# signal-1btn.net
KiCad netlist of a schematic drawn in EAGLE
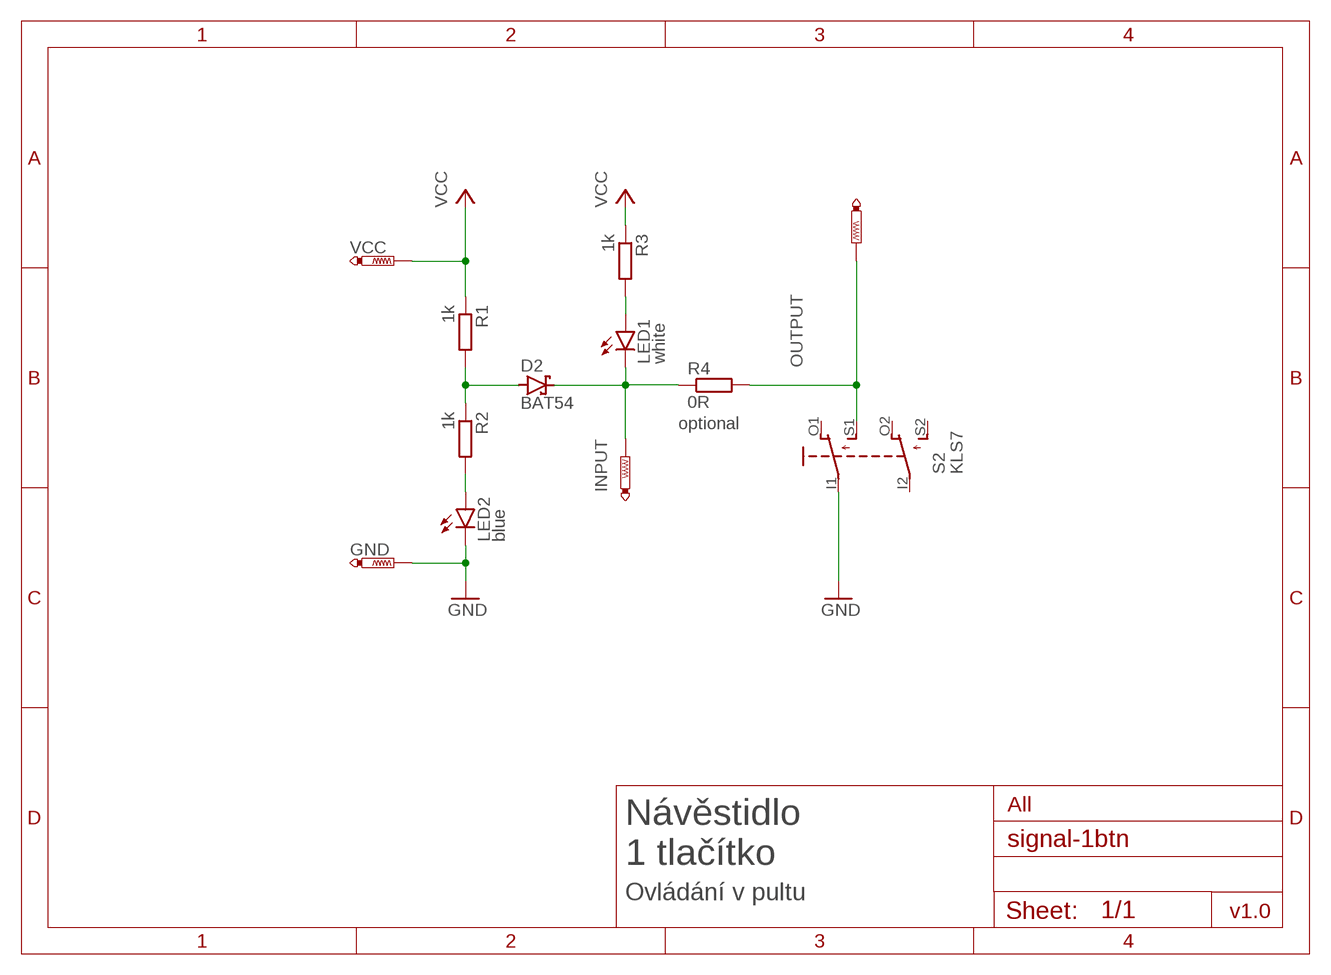
[diagram p0: schematic, sheet 1]

(export (version "E")
  (design (tool "Eeschema 10.0.6"))
  (components
    (comp (ref "D2")
      (value "BAT54")
      (footprint "eagle-import:SOT23")
      (libsource (lib "eagle-import") (part "BAT54"))
    )
    (comp (ref "GND")
      (value "PTR1PAD1-13Y")
      (footprint "eagle-import:P1-13Y")
      (libsource (lib "eagle-import") (part "PTR1PAD1-13Y"))
    )
    (comp (ref "LED1")
      (value "white")
      (footprint "eagle-import:LED3MM")
      (libsource (lib "eagle-import") (part "LED3MM"))
    )
    (comp (ref "LED2")
      (value "blue")
      (footprint "eagle-import:LED3MM")
      (libsource (lib "eagle-import") (part "LED3MM"))
    )
    (comp (ref "P_ACTIVE")
      (value "PTR1PAD1-13Y")
      (footprint "eagle-import:P1-13Y")
      (libsource (lib "eagle-import") (part "PTR1PAD1-13Y"))
    )
    (comp (ref "P_ACTIVE1")
      (value "PTR1PAD1-13Y")
      (footprint "eagle-import:P1-13Y")
      (libsource (lib "eagle-import") (part "PTR1PAD1-13Y"))
    )
    (comp (ref "R1")
      (value "1k")
      (footprint "eagle-import:R0805")
      (libsource (lib "eagle-import") (part "R-EU_R0805"))
    )
    (comp (ref "R2")
      (value "1k")
      (footprint "eagle-import:R0805")
      (libsource (lib "eagle-import") (part "R-EU_R0805"))
    )
    (comp (ref "R3")
      (value "1k")
      (footprint "eagle-import:R0805")
      (libsource (lib "eagle-import") (part "R-EU_R0805"))
    )
    (comp (ref "R4")
      (value "0R")
      (footprint "eagle-import:R0805")
      (libsource (lib "eagle-import") (part "R-EU_R0805"))
    )
    (comp (ref "S2")
      (value "KLS7")
      (footprint "eagle-import:KLS7")
      (libsource (lib "eagle-import") (part "KLS7"))
    )
    (comp (ref "VCC")
      (value "PTR1PAD1-13Y")
      (footprint "eagle-import:P1-13Y")
      (libsource (lib "eagle-import") (part "PTR1PAD1-13Y"))
    )
  )
  (nets
    (net (code "1") (name "/INPUT") (class "Default")
      (node (ref "D2") (pin "3") (pinfunction "C_3") (pintype "passive"))
      (node (ref "LED1") (pin "K") (pinfunction "C_K") (pintype "passive"))
      (node (ref "P_ACTIVE1") (pin "TP") (pinfunction "TP_TP") (pintype "input"))
      (node (ref "R4") (pin "1") (pinfunction "1_1") (pintype "passive"))
    )
    (net (code "2") (name "/OUTPUT") (class "Default")
      (node (ref "P_ACTIVE") (pin "TP") (pinfunction "TP_TP") (pintype "input"))
      (node (ref "R4") (pin "2") (pinfunction "2_2") (pintype "passive"))
      (node (ref "S2") (pin "S1") (pinfunction "S_S1") (pintype "passive"))
    )
    (net (code "3") (name "GND") (class "Default")
      (node (ref "GND") (pin "TP") (pinfunction "TP_TP") (pintype "input"))
      (node (ref "LED2") (pin "K") (pinfunction "C_K") (pintype "passive"))
      (node (ref "S2") (pin "I1") (pinfunction "P_I1") (pintype "passive"))
    )
    (net (code "4") (name "Net-(D2-A)") (class "Default")
      (node (ref "D2") (pin "1") (pinfunction "A_1") (pintype "passive"))
      (node (ref "R1") (pin "2") (pinfunction "2_2") (pintype "passive"))
      (node (ref "R2") (pin "1") (pinfunction "1_1") (pintype "passive"))
    )
    (net (code "5") (name "Net-(LED1-PadA)") (class "Default")
      (node (ref "LED1") (pin "A") (pinfunction "A_A") (pintype "passive"))
      (node (ref "R3") (pin "2") (pinfunction "2_2") (pintype "passive"))
    )
    (net (code "6") (name "Net-(LED2-PadA)") (class "Default")
      (node (ref "LED2") (pin "A") (pinfunction "A_A") (pintype "passive"))
      (node (ref "R2") (pin "2") (pinfunction "2_2") (pintype "passive"))
    )
    (net (code "7") (name "VCC") (class "Default")
      (node (ref "R1") (pin "1") (pinfunction "1_1") (pintype "passive"))
      (node (ref "R3") (pin "1") (pinfunction "1_1") (pintype "passive"))
      (node (ref "VCC") (pin "TP") (pinfunction "TP_TP") (pintype "input"))
    )
    (net (code "8") (name "unconnected-(S2-O-PadO1)") (class "Default")
      (node (ref "S2") (pin "O1") (pinfunction "O_O1") (pintype "passive"))
    )
    (net (code "9") (name "unconnected-(S2-O1-PadO2)") (class "Default")
      (node (ref "S2") (pin "O2") (pinfunction "O1_O2") (pintype "passive"))
    )
    (net (code "10") (name "unconnected-(S2-P1-PadI2)") (class "Default")
      (node (ref "S2") (pin "I2") (pinfunction "P1_I2") (pintype "passive"))
    )
    (net (code "11") (name "unconnected-(S2-S1-PadS2)") (class "Default")
      (node (ref "S2") (pin "S2") (pinfunction "S1_S2") (pintype "passive"))
    )
  )
)
